# bank_35.net
KiCad netlist of a schematic drawn in Altium Designer
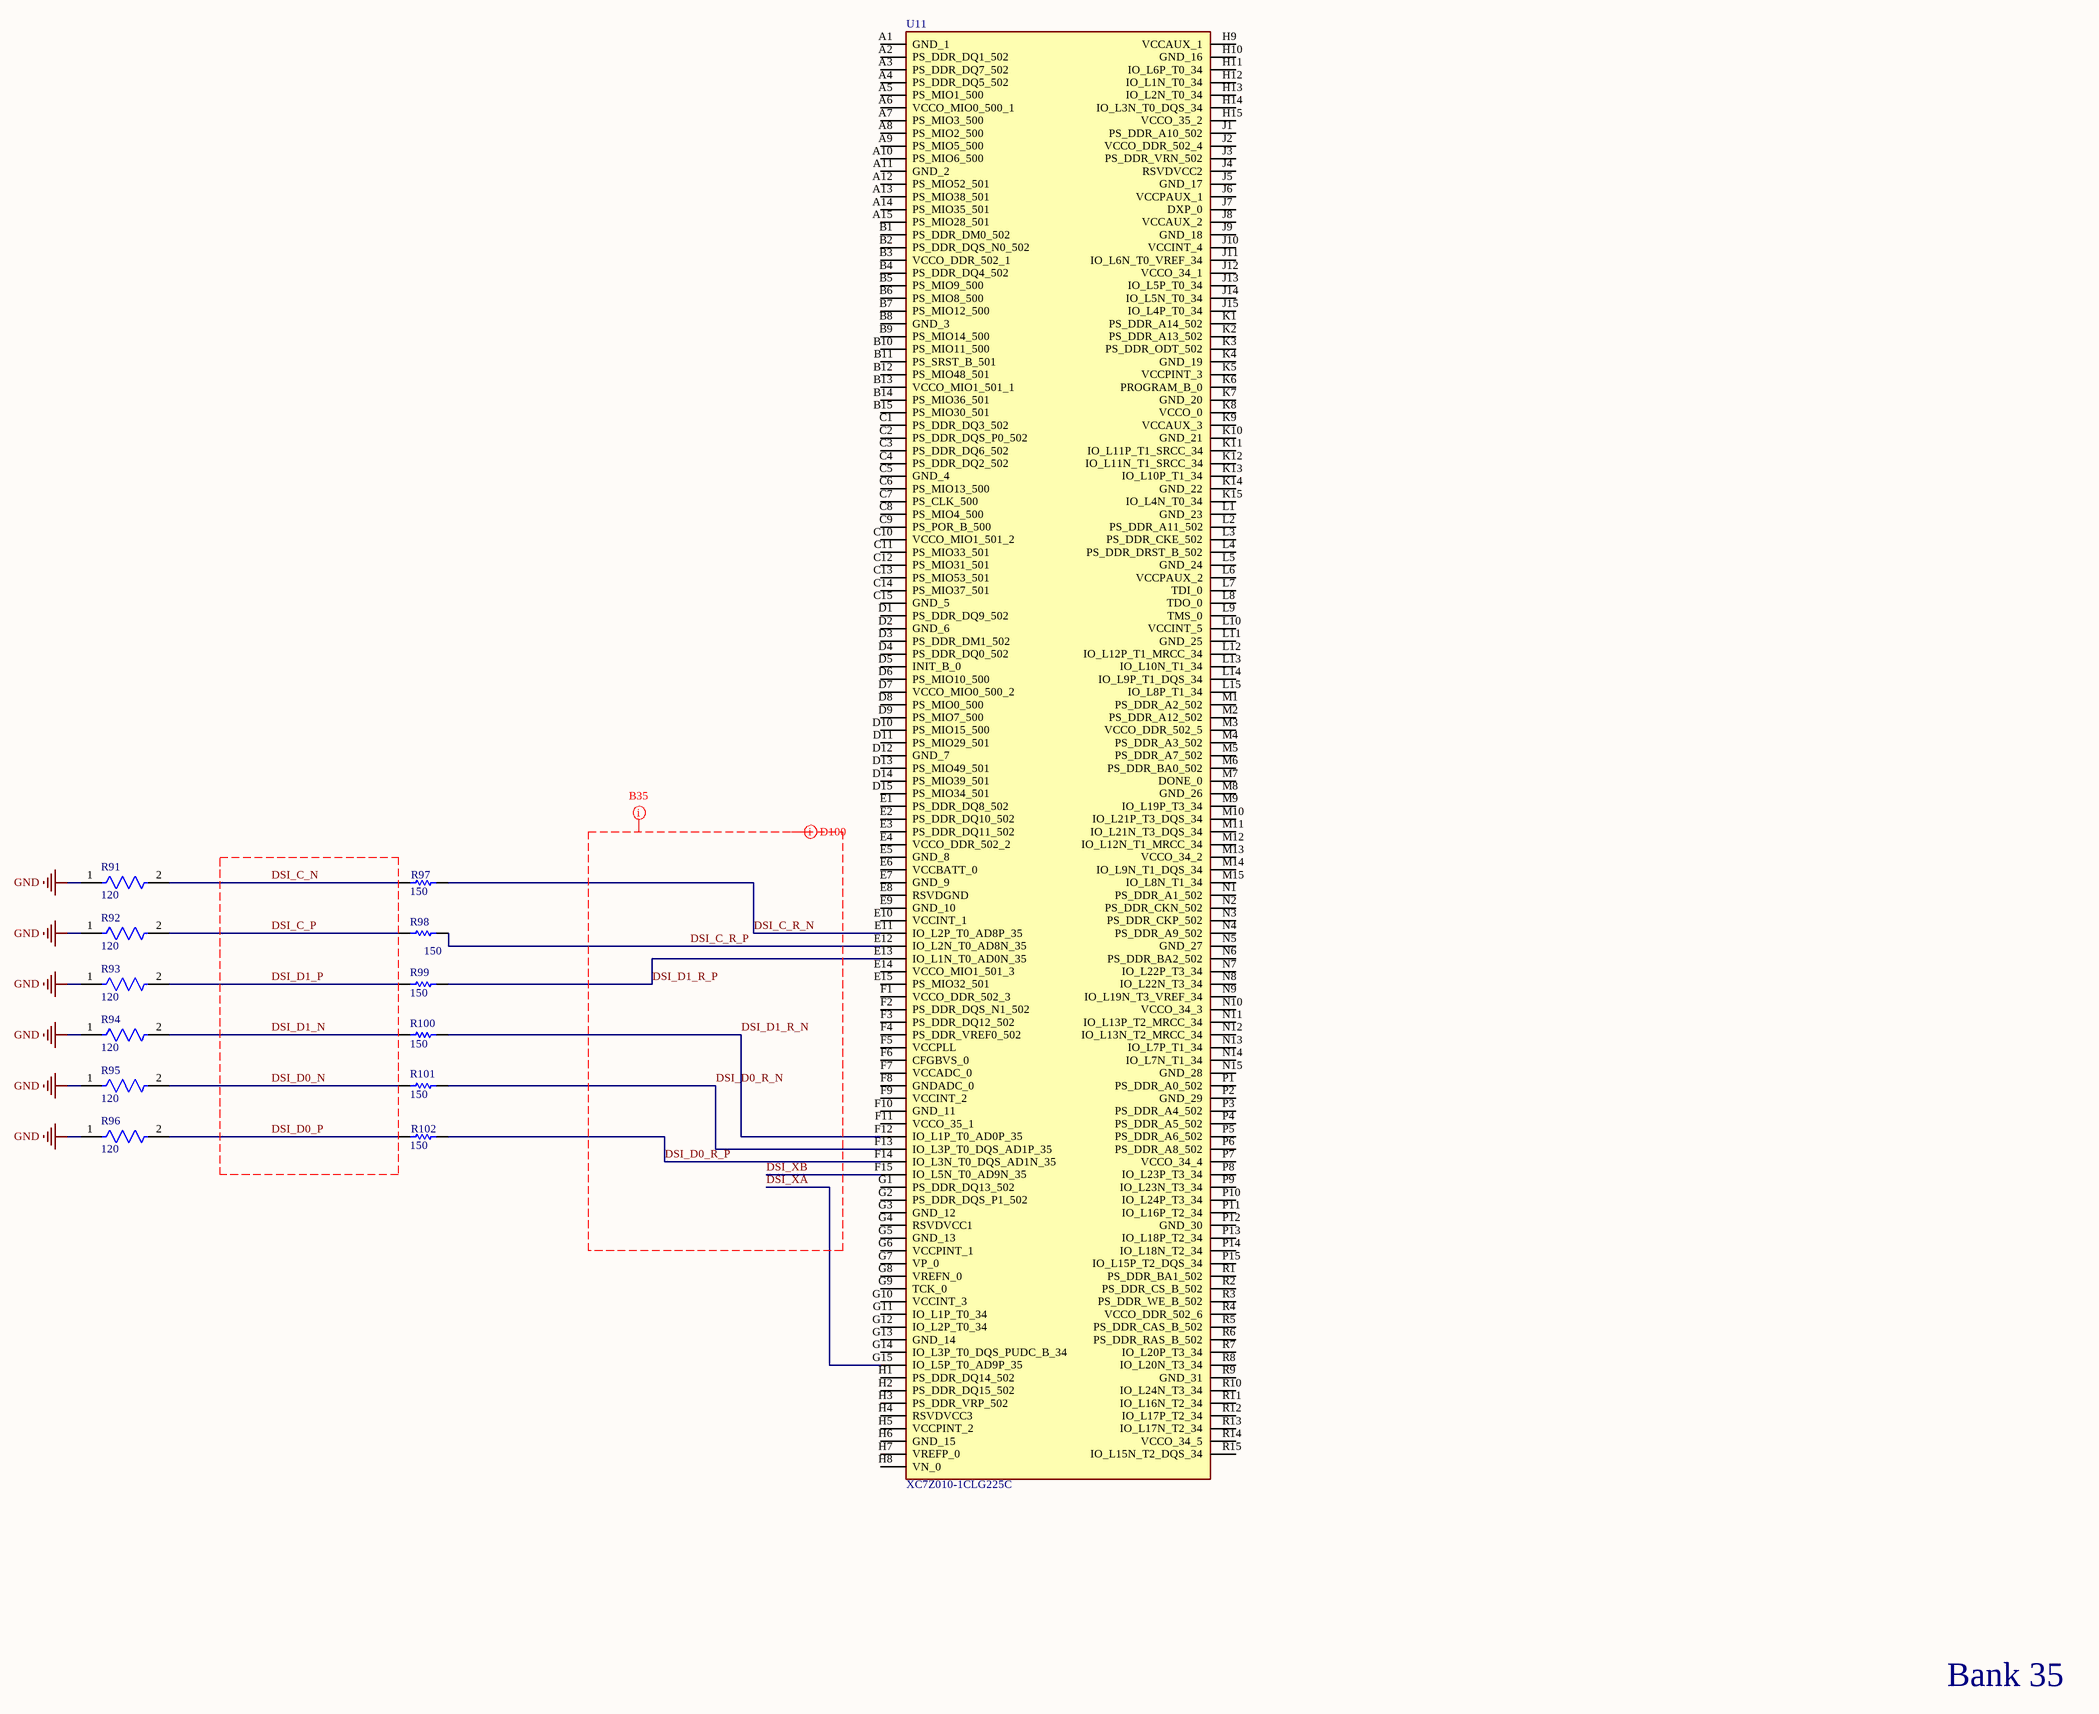
[diagram p0: bank 35.SchDoc]

(export (version "E")
  (design (tool "Eeschema 10.0.6"))
  (components
    (comp (ref "R91")
      (value "120")
      (footprint "FP-CR1206-MFG")
      (description "Thick Film Chip Resistors 1206 120Ω 0.25W 1% 100ppm/°C")
      (fields (field (name "TOLERANCE") "1%"))
      (libsource (lib "Altium Content Vault") (part "1029c3af85768c4190bb7ad29bc67b5"))
    )
    (comp (ref "R92")
      (value "120")
      (footprint "FP-CR1206-MFG")
      (description "Thick Film Chip Resistors 1206 120Ω 0.25W 1% 100ppm/°C")
      (fields (field (name "TOLERANCE") "1%"))
      (libsource (lib "Altium Content Vault") (part "1029c3af85768c4190bb7ad29bc67b5"))
    )
    (comp (ref "R93")
      (value "120")
      (footprint "FP-CR1206-MFG")
      (description "Thick Film Chip Resistors 1206 120Ω 0.25W 1% 100ppm/°C")
      (fields (field (name "TOLERANCE") "1%"))
      (libsource (lib "Altium Content Vault") (part "1029c3af85768c4190bb7ad29bc67b5"))
    )
    (comp (ref "R94")
      (value "120")
      (footprint "FP-CR1206-MFG")
      (description "Thick Film Chip Resistors 1206 120Ω 0.25W 1% 100ppm/°C")
      (fields (field (name "TOLERANCE") "1%"))
      (libsource (lib "Altium Content Vault") (part "1029c3af85768c4190bb7ad29bc67b5"))
    )
    (comp (ref "R95")
      (value "120")
      (footprint "FP-CR1206-MFG")
      (description "Thick Film Chip Resistors 1206 120Ω 0.25W 1% 100ppm/°C")
      (fields (field (name "TOLERANCE") "1%"))
      (libsource (lib "Altium Content Vault") (part "1029c3af85768c4190bb7ad29bc67b5"))
    )
    (comp (ref "R96")
      (value "120")
      (footprint "FP-CR1206-MFG")
      (description "Thick Film Chip Resistors 1206 120Ω 0.25W 1% 100ppm/°C")
      (fields (field (name "TOLERANCE") "1%"))
      (libsource (lib "Altium Content Vault") (part "1029c3af85768c4190bb7ad29bc67b5"))
    )
    (comp (ref "R97")
      (value "150")
      (footprint "RESC1609X55X30NL10T20")
      (fields (field (name "MANUFACTURER") "Vishay Dale") (field (name "PART NUMBER") "TNPW0603150RBETA"))
      (libsource (lib "Altium Content Vault") (part "RES"))
    )
    (comp (ref "R98")
      (value "150")
      (footprint "RESC1609X55X30NL10T20")
      (fields (field (name "MANUFACTURER") "Vishay Dale") (field (name "PART NUMBER") "TNPW0603150RBETA"))
      (libsource (lib "Altium Content Vault") (part "RES"))
    )
    (comp (ref "R99")
      (value "150")
      (footprint "RESC1609X55X30NL10T20")
      (fields (field (name "MANUFACTURER") "Vishay Dale") (field (name "PART NUMBER") "TNPW0603150RBETA"))
      (libsource (lib "Altium Content Vault") (part "RES"))
    )
    (comp (ref "R100")
      (value "150")
      (footprint "RESC1609X55X30NL10T20")
      (fields (field (name "MANUFACTURER") "Vishay Dale") (field (name "PART NUMBER") "TNPW0603150RBETA"))
      (libsource (lib "Altium Content Vault") (part "RES"))
    )
    (comp (ref "R101")
      (value "150")
      (footprint "RESC1609X55X30NL10T20")
      (fields (field (name "MANUFACTURER") "Vishay Dale") (field (name "PART NUMBER") "TNPW0603150RBETA"))
      (libsource (lib "Altium Content Vault") (part "RES"))
    )
    (comp (ref "R102")
      (value "150")
      (footprint "RESC1609X55X30NL10T20")
      (fields (field (name "MANUFACTURER") "Vishay Dale") (field (name "PART NUMBER") "TNPW0603150RBETA"))
      (libsource (lib "Altium Content Vault") (part "RES"))
    )
    (comp (ref "U11")
      (value "XC7Z010-1CLG225C")
      (footprint "SamacSys:BGA225C80P15X15_1300X1300X140")
      (description "Integrated Circuit")
      (fields (field (name "MOUSER PART NUMBER") "217-XC7Z010-1CLG225C"))
      (libsource (lib "*") (part "XC7Z010-1CLG225C"))
    )
  )
  (nets
    (net (code "1") (name "/DSI_C_N") (class "Default")
      (node (ref "R91") (pin "2") (pinfunction "2_2") (pintype "passive"))
      (node (ref "R97") (pin "1") (pinfunction "1_1") (pintype "passive"))
    )
    (net (code "2") (name "/DSI_C_P") (class "Default")
      (node (ref "R92") (pin "2") (pinfunction "2_2") (pintype "passive"))
      (node (ref "R98") (pin "1") (pinfunction "1_1") (pintype "passive"))
    )
    (net (code "3") (name "/DSI_C_R_N") (class "Default")
      (node (ref "R97") (pin "2") (pinfunction "2_2") (pintype "passive"))
      (node (ref "U11") (pin "E11") (pinfunction "IO_L2P_T0_AD8P_35_E11") (pintype "passive"))
    )
    (net (code "4") (name "/DSI_C_R_P") (class "Default")
      (node (ref "R98") (pin "2") (pinfunction "2_2") (pintype "passive"))
      (node (ref "U11") (pin "E12") (pinfunction "IO_L2N_T0_AD8N_35_E12") (pintype "passive"))
    )
    (net (code "5") (name "/DSI_D0_N") (class "Default")
      (node (ref "R101") (pin "1") (pinfunction "1_1") (pintype "passive"))
      (node (ref "R95") (pin "2") (pinfunction "2_2") (pintype "passive"))
    )
    (net (code "6") (name "/DSI_D0_P") (class "Default")
      (node (ref "R102") (pin "1") (pinfunction "1_1") (pintype "passive"))
      (node (ref "R96") (pin "2") (pinfunction "2_2") (pintype "passive"))
    )
    (net (code "7") (name "/DSI_D0_R_N") (class "Default")
      (node (ref "R101") (pin "2") (pinfunction "2_2") (pintype "passive"))
      (node (ref "U11") (pin "F13") (pinfunction "IO_L3P_T0_DQS_AD1P_35_F13") (pintype "passive"))
    )
    (net (code "8") (name "/DSI_D0_R_P") (class "Default")
      (node (ref "R102") (pin "2") (pinfunction "2_2") (pintype "passive"))
      (node (ref "U11") (pin "F14") (pinfunction "IO_L3N_T0_DQS_AD1N_35_F14") (pintype "passive"))
    )
    (net (code "9") (name "/DSI_D1_N") (class "Default")
      (node (ref "R100") (pin "1") (pinfunction "1_1") (pintype "passive"))
      (node (ref "R94") (pin "2") (pinfunction "2_2") (pintype "passive"))
    )
    (net (code "10") (name "/DSI_D1_P") (class "Default")
      (node (ref "R93") (pin "2") (pinfunction "2_2") (pintype "passive"))
      (node (ref "R99") (pin "1") (pinfunction "1_1") (pintype "passive"))
    )
    (net (code "11") (name "/DSI_D1_R_N") (class "Default")
      (node (ref "R100") (pin "2") (pinfunction "2_2") (pintype "passive"))
      (node (ref "U11") (pin "F12") (pinfunction "IO_L1P_T0_AD0P_35_F12") (pintype "passive"))
    )
    (net (code "12") (name "/DSI_D1_R_P") (class "Default")
      (node (ref "R99") (pin "2") (pinfunction "2_2") (pintype "passive"))
      (node (ref "U11") (pin "E13") (pinfunction "IO_L1N_T0_AD0N_35_E13") (pintype "passive"))
    )
    (net (code "13") (name "/DSI_XA") (class "Default")
      (node (ref "U11") (pin "G15") (pinfunction "IO_L5P_T0_AD9P_35_G15") (pintype "passive"))
    )
    (net (code "14") (name "/DSI_XB") (class "Default")
      (node (ref "U11") (pin "F15") (pinfunction "IO_L5N_T0_AD9N_35_F15") (pintype "passive"))
    )
    (net (code "15") (name "GND") (class "Default")
      (node (ref "R91") (pin "1") (pinfunction "1_1") (pintype "passive"))
      (node (ref "R92") (pin "1") (pinfunction "1_1") (pintype "passive"))
      (node (ref "R93") (pin "1") (pinfunction "1_1") (pintype "passive"))
      (node (ref "R94") (pin "1") (pinfunction "1_1") (pintype "passive"))
      (node (ref "R95") (pin "1") (pinfunction "1_1") (pintype "passive"))
      (node (ref "R96") (pin "1") (pinfunction "1_1") (pintype "passive"))
    )
    (net (code "16") (name "unconnected-(U11-CFGBVS_0-PadF6)") (class "Default")
      (node (ref "U11") (pin "F6") (pinfunction "CFGBVS_0_F6") (pintype "passive"))
    )
    (net (code "17") (name "unconnected-(U11-DONE_0-PadM7)") (class "Default")
      (node (ref "U11") (pin "M7") (pinfunction "DONE_0_M7") (pintype "passive"))
    )
    (net (code "18") (name "unconnected-(U11-DXP_0-PadJ7)") (class "Default")
      (node (ref "U11") (pin "J7") (pinfunction "DXP_0_J7") (pintype "passive"))
    )
    (net (code "19") (name "unconnected-(U11-GNDADC_0-PadF8)") (class "Default")
      (node (ref "U11") (pin "F8") (pinfunction "GNDADC_0_F8") (pintype "passive"))
    )
    (net (code "20") (name "unconnected-(U11-GND_1-PadA1)") (class "Default")
      (node (ref "U11") (pin "A1") (pinfunction "GND_1_A1") (pintype "passive"))
    )
    (net (code "21") (name "unconnected-(U11-GND_2-PadA11)") (class "Default")
      (node (ref "U11") (pin "A11") (pinfunction "GND_2_A11") (pintype "passive"))
    )
    (net (code "22") (name "unconnected-(U11-GND_3-PadB8)") (class "Default")
      (node (ref "U11") (pin "B8") (pinfunction "GND_3_B8") (pintype "passive"))
    )
    (net (code "23") (name "unconnected-(U11-GND_4-PadC5)") (class "Default")
      (node (ref "U11") (pin "C5") (pinfunction "GND_4_C5") (pintype "passive"))
    )
    (net (code "24") (name "unconnected-(U11-GND_5-PadC15)") (class "Default")
      (node (ref "U11") (pin "C15") (pinfunction "GND_5_C15") (pintype "passive"))
    )
    (net (code "25") (name "unconnected-(U11-GND_6-PadD2)") (class "Default")
      (node (ref "U11") (pin "D2") (pinfunction "GND_6_D2") (pintype "passive"))
    )
    (net (code "26") (name "unconnected-(U11-GND_7-PadD12)") (class "Default")
      (node (ref "U11") (pin "D12") (pinfunction "GND_7_D12") (pintype "passive"))
    )
    (net (code "27") (name "unconnected-(U11-GND_8-PadE5)") (class "Default")
      (node (ref "U11") (pin "E5") (pinfunction "GND_8_E5") (pintype "passive"))
    )
    (net (code "28") (name "unconnected-(U11-GND_9-PadE7)") (class "Default")
      (node (ref "U11") (pin "E7") (pinfunction "GND_9_E7") (pintype "passive"))
    )
    (net (code "29") (name "unconnected-(U11-GND_10-PadE9)") (class "Default")
      (node (ref "U11") (pin "E9") (pinfunction "GND_10_E9") (pintype "passive"))
    )
    (net (code "30") (name "unconnected-(U11-GND_11-PadF10)") (class "Default")
      (node (ref "U11") (pin "F10") (pinfunction "GND_11_F10") (pintype "passive"))
    )
    (net (code "31") (name "unconnected-(U11-GND_12-PadG3)") (class "Default")
      (node (ref "U11") (pin "G3") (pinfunction "GND_12_G3") (pintype "passive"))
    )
    (net (code "32") (name "unconnected-(U11-GND_13-PadG5)") (class "Default")
      (node (ref "U11") (pin "G5") (pinfunction "GND_13_G5") (pintype "passive"))
    )
    (net (code "33") (name "unconnected-(U11-GND_14-PadG13)") (class "Default")
      (node (ref "U11") (pin "G13") (pinfunction "GND_14_G13") (pintype "passive"))
    )
    (net (code "34") (name "unconnected-(U11-GND_15-PadH6)") (class "Default")
      (node (ref "U11") (pin "H6") (pinfunction "GND_15_H6") (pintype "passive"))
    )
    (net (code "35") (name "unconnected-(U11-GND_16-PadH10)") (class "Default")
      (node (ref "U11") (pin "H10") (pinfunction "GND_16_H10") (pintype "passive"))
    )
    (net (code "36") (name "unconnected-(U11-GND_17-PadJ5)") (class "Default")
      (node (ref "U11") (pin "J5") (pinfunction "GND_17_J5") (pintype "passive"))
    )
    (net (code "37") (name "unconnected-(U11-GND_18-PadJ9)") (class "Default")
      (node (ref "U11") (pin "J9") (pinfunction "GND_18_J9") (pintype "passive"))
    )
    (net (code "38") (name "unconnected-(U11-GND_19-PadK4)") (class "Default")
      (node (ref "U11") (pin "K4") (pinfunction "GND_19_K4") (pintype "passive"))
    )
    (net (code "39") (name "unconnected-(U11-GND_20-PadK7)") (class "Default")
      (node (ref "U11") (pin "K7") (pinfunction "GND_20_K7") (pintype "passive"))
    )
    (net (code "40") (name "unconnected-(U11-GND_21-PadK10)") (class "Default")
      (node (ref "U11") (pin "K10") (pinfunction "GND_21_K10") (pintype "passive"))
    )
    (net (code "41") (name "unconnected-(U11-GND_22-PadK14)") (class "Default")
      (node (ref "U11") (pin "K14") (pinfunction "GND_22_K14") (pintype "passive"))
    )
    (net (code "42") (name "unconnected-(U11-GND_23-PadL1)") (class "Default")
      (node (ref "U11") (pin "L1") (pinfunction "GND_23_L1") (pintype "passive"))
    )
    (net (code "43") (name "unconnected-(U11-GND_24-PadL5)") (class "Default")
      (node (ref "U11") (pin "L5") (pinfunction "GND_24_L5") (pintype "passive"))
    )
    (net (code "44") (name "unconnected-(U11-GND_25-PadL11)") (class "Default")
      (node (ref "U11") (pin "L11") (pinfunction "GND_25_L11") (pintype "passive"))
    )
    (net (code "45") (name "unconnected-(U11-GND_26-PadM8)") (class "Default")
      (node (ref "U11") (pin "M8") (pinfunction "GND_26_M8") (pintype "passive"))
    )
    (net (code "46") (name "unconnected-(U11-GND_27-PadN5)") (class "Default")
      (node (ref "U11") (pin "N5") (pinfunction "GND_27_N5") (pintype "passive"))
    )
    (net (code "47") (name "unconnected-(U11-GND_28-PadN15)") (class "Default")
      (node (ref "U11") (pin "N15") (pinfunction "GND_28_N15") (pintype "passive"))
    )
    (net (code "48") (name "unconnected-(U11-GND_29-PadP2)") (class "Default")
      (node (ref "U11") (pin "P2") (pinfunction "GND_29_P2") (pintype "passive"))
    )
    (net (code "49") (name "unconnected-(U11-GND_30-PadP12)") (class "Default")
      (node (ref "U11") (pin "P12") (pinfunction "GND_30_P12") (pintype "passive"))
    )
    (net (code "50") (name "unconnected-(U11-GND_31-PadR9)") (class "Default")
      (node (ref "U11") (pin "R9") (pinfunction "GND_31_R9") (pintype "passive"))
    )
    (net (code "51") (name "unconnected-(U11-INIT_B_0-PadD5)") (class "Default")
      (node (ref "U11") (pin "D5") (pinfunction "INIT_B_0_D5") (pintype "passive"))
    )
    (net (code "52") (name "unconnected-(U11-IO_L1N_T0_34-PadH12)") (class "Default")
      (node (ref "U11") (pin "H12") (pinfunction "IO_L1N_T0_34_H12") (pintype "passive"))
    )
    (net (code "53") (name "unconnected-(U11-IO_L1P_T0_34-PadG11)") (class "Default")
      (node (ref "U11") (pin "G11") (pinfunction "IO_L1P_T0_34_G11") (pintype "passive"))
    )
    (net (code "54") (name "unconnected-(U11-IO_L2N_T0_34-PadH13)") (class "Default")
      (node (ref "U11") (pin "H13") (pinfunction "IO_L2N_T0_34_H13") (pintype "passive"))
    )
    (net (code "55") (name "unconnected-(U11-IO_L2P_T0_34-PadG12)") (class "Default")
      (node (ref "U11") (pin "G12") (pinfunction "IO_L2P_T0_34_G12") (pintype "passive"))
    )
    (net (code "56") (name "unconnected-(U11-IO_L3N_T0_DQS_34-PadH14)") (class "Default")
      (node (ref "U11") (pin "H14") (pinfunction "IO_L3N_T0_DQS_34_H14") (pintype "passive"))
    )
    (net (code "57") (name "unconnected-(U11-IO_L3P_T0_DQS_PUDC_B_34-PadG14)") (class "Default")
      (node (ref "U11") (pin "G14") (pinfunction "IO_L3P_T0_DQS_PUDC_B_34_G14") (pintype "passive"))
    )
    (net (code "58") (name "unconnected-(U11-IO_L4N_T0_34-PadK15)") (class "Default")
      (node (ref "U11") (pin "K15") (pinfunction "IO_L4N_T0_34_K15") (pintype "passive"))
    )
    (net (code "59") (name "unconnected-(U11-IO_L4P_T0_34-PadJ15)") (class "Default")
      (node (ref "U11") (pin "J15") (pinfunction "IO_L4P_T0_34_J15") (pintype "passive"))
    )
    (net (code "60") (name "unconnected-(U11-IO_L5N_T0_34-PadJ14)") (class "Default")
      (node (ref "U11") (pin "J14") (pinfunction "IO_L5N_T0_34_J14") (pintype "passive"))
    )
    (net (code "61") (name "unconnected-(U11-IO_L5P_T0_34-PadJ13)") (class "Default")
      (node (ref "U11") (pin "J13") (pinfunction "IO_L5P_T0_34_J13") (pintype "passive"))
    )
    (net (code "62") (name "unconnected-(U11-IO_L6N_T0_VREF_34-PadJ11)") (class "Default")
      (node (ref "U11") (pin "J11") (pinfunction "IO_L6N_T0_VREF_34_J11") (pintype "passive"))
    )
    (net (code "63") (name "unconnected-(U11-IO_L6P_T0_34-PadH11)") (class "Default")
      (node (ref "U11") (pin "H11") (pinfunction "IO_L6P_T0_34_H11") (pintype "passive"))
    )
    (net (code "64") (name "unconnected-(U11-IO_L7N_T1_34-PadN14)") (class "Default")
      (node (ref "U11") (pin "N14") (pinfunction "IO_L7N_T1_34_N14") (pintype "passive"))
    )
    (net (code "65") (name "unconnected-(U11-IO_L7P_T1_34-PadN13)") (class "Default")
      (node (ref "U11") (pin "N13") (pinfunction "IO_L7P_T1_34_N13") (pintype "passive"))
    )
    (net (code "66") (name "unconnected-(U11-IO_L8N_T1_34-PadM15)") (class "Default")
      (node (ref "U11") (pin "M15") (pinfunction "IO_L8N_T1_34_M15") (pintype "passive"))
    )
    (net (code "67") (name "unconnected-(U11-IO_L8P_T1_34-PadL15)") (class "Default")
      (node (ref "U11") (pin "L15") (pinfunction "IO_L8P_T1_34_L15") (pintype "passive"))
    )
    (net (code "68") (name "unconnected-(U11-IO_L9N_T1_DQS_34-PadM14)") (class "Default")
      (node (ref "U11") (pin "M14") (pinfunction "IO_L9N_T1_DQS_34_M14") (pintype "passive"))
    )
    (net (code "69") (name "unconnected-(U11-IO_L9P_T1_DQS_34-PadL14)") (class "Default")
      (node (ref "U11") (pin "L14") (pinfunction "IO_L9P_T1_DQS_34_L14") (pintype "passive"))
    )
    (net (code "70") (name "unconnected-(U11-IO_L10N_T1_34-PadL13)") (class "Default")
      (node (ref "U11") (pin "L13") (pinfunction "IO_L10N_T1_34_L13") (pintype "passive"))
    )
    (net (code "71") (name "unconnected-(U11-IO_L10P_T1_34-PadK13)") (class "Default")
      (node (ref "U11") (pin "K13") (pinfunction "IO_L10P_T1_34_K13") (pintype "passive"))
    )
    (net (code "72") (name "unconnected-(U11-IO_L11N_T1_SRCC_34-PadK12)") (class "Default")
      (node (ref "U11") (pin "K12") (pinfunction "IO_L11N_T1_SRCC_34_K12") (pintype "passive"))
    )
    (net (code "73") (name "unconnected-(U11-IO_L11P_T1_SRCC_34-PadK11)") (class "Default")
      (node (ref "U11") (pin "K11") (pinfunction "IO_L11P_T1_SRCC_34_K11") (pintype "passive"))
    )
    (net (code "74") (name "unconnected-(U11-IO_L12N_T1_MRCC_34-PadM12)") (class "Default")
      (node (ref "U11") (pin "M12") (pinfunction "IO_L12N_T1_MRCC_34_M12") (pintype "passive"))
    )
    (net (code "75") (name "unconnected-(U11-IO_L12P_T1_MRCC_34-PadL12)") (class "Default")
      (node (ref "U11") (pin "L12") (pinfunction "IO_L12P_T1_MRCC_34_L12") (pintype "passive"))
    )
    (net (code "76") (name "unconnected-(U11-IO_L13N_T2_MRCC_34-PadN12)") (class "Default")
      (node (ref "U11") (pin "N12") (pinfunction "IO_L13N_T2_MRCC_34_N12") (pintype "passive"))
    )
    (net (code "77") (name "unconnected-(U11-IO_L13P_T2_MRCC_34-PadN11)") (class "Default")
      (node (ref "U11") (pin "N11") (pinfunction "IO_L13P_T2_MRCC_34_N11") (pintype "passive"))
    )
    (net (code "78") (name "unconnected-(U11-IO_L15N_T2_DQS_34-PadR15)") (class "Default")
      (node (ref "U11") (pin "R15") (pinfunction "IO_L15N_T2_DQS_34_R15") (pintype "passive"))
    )
    (net (code "79") (name "unconnected-(U11-IO_L15P_T2_DQS_34-PadP15)") (class "Default")
      (node (ref "U11") (pin "P15") (pinfunction "IO_L15P_T2_DQS_34_P15") (pintype "passive"))
    )
    (net (code "80") (name "unconnected-(U11-IO_L16N_T2_34-PadR11)") (class "Default")
      (node (ref "U11") (pin "R11") (pinfunction "IO_L16N_T2_34_R11") (pintype "passive"))
    )
    (net (code "81") (name "unconnected-(U11-IO_L16P_T2_34-PadP11)") (class "Default")
      (node (ref "U11") (pin "P11") (pinfunction "IO_L16P_T2_34_P11") (pintype "passive"))
    )
    (net (code "82") (name "unconnected-(U11-IO_L17N_T2_34-PadR13)") (class "Default")
      (node (ref "U11") (pin "R13") (pinfunction "IO_L17N_T2_34_R13") (pintype "passive"))
    )
    (net (code "83") (name "unconnected-(U11-IO_L17P_T2_34-PadR12)") (class "Default")
      (node (ref "U11") (pin "R12") (pinfunction "IO_L17P_T2_34_R12") (pintype "passive"))
    )
    (net (code "84") (name "unconnected-(U11-IO_L18N_T2_34-PadP14)") (class "Default")
      (node (ref "U11") (pin "P14") (pinfunction "IO_L18N_T2_34_P14") (pintype "passive"))
    )
    (net (code "85") (name "unconnected-(U11-IO_L18P_T2_34-PadP13)") (class "Default")
      (node (ref "U11") (pin "P13") (pinfunction "IO_L18P_T2_34_P13") (pintype "passive"))
    )
    (net (code "86") (name "unconnected-(U11-IO_L19N_T3_VREF_34-PadN9)") (class "Default")
      (node (ref "U11") (pin "N9") (pinfunction "IO_L19N_T3_VREF_34_N9") (pintype "passive"))
    )
    (net (code "87") (name "unconnected-(U11-IO_L19P_T3_34-PadM9)") (class "Default")
      (node (ref "U11") (pin "M9") (pinfunction "IO_L19P_T3_34_M9") (pintype "passive"))
    )
    (net (code "88") (name "unconnected-(U11-IO_L20N_T3_34-PadR8)") (class "Default")
      (node (ref "U11") (pin "R8") (pinfunction "IO_L20N_T3_34_R8") (pintype "passive"))
    )
    (net (code "89") (name "unconnected-(U11-IO_L20P_T3_34-PadR7)") (class "Default")
      (node (ref "U11") (pin "R7") (pinfunction "IO_L20P_T3_34_R7") (pintype "passive"))
    )
    (net (code "90") (name "unconnected-(U11-IO_L21N_T3_DQS_34-PadM11)") (class "Default")
      (node (ref "U11") (pin "M11") (pinfunction "IO_L21N_T3_DQS_34_M11") (pintype "passive"))
    )
    (net (code "91") (name "unconnected-(U11-IO_L21P_T3_DQS_34-PadM10)") (class "Default")
      (node (ref "U11") (pin "M10") (pinfunction "IO_L21P_T3_DQS_34_M10") (pintype "passive"))
    )
    (net (code "92") (name "unconnected-(U11-IO_L22N_T3_34-PadN8)") (class "Default")
      (node (ref "U11") (pin "N8") (pinfunction "IO_L22N_T3_34_N8") (pintype "passive"))
    )
    (net (code "93") (name "unconnected-(U11-IO_L22P_T3_34-PadN7)") (class "Default")
      (node (ref "U11") (pin "N7") (pinfunction "IO_L22P_T3_34_N7") (pintype "passive"))
    )
    (net (code "94") (name "unconnected-(U11-IO_L23N_T3_34-PadP9)") (class "Default")
      (node (ref "U11") (pin "P9") (pinfunction "IO_L23N_T3_34_P9") (pintype "passive"))
    )
    (net (code "95") (name "unconnected-(U11-IO_L23P_T3_34-PadP8)") (class "Default")
      (node (ref "U11") (pin "P8") (pinfunction "IO_L23P_T3_34_P8") (pintype "passive"))
    )
    (net (code "96") (name "unconnected-(U11-IO_L24N_T3_34-PadR10)") (class "Default")
      (node (ref "U11") (pin "R10") (pinfunction "IO_L24N_T3_34_R10") (pintype "passive"))
    )
    (net (code "97") (name "unconnected-(U11-IO_L24P_T3_34-PadP10)") (class "Default")
      (node (ref "U11") (pin "P10") (pinfunction "IO_L24P_T3_34_P10") (pintype "passive"))
    )
    (net (code "98") (name "unconnected-(U11-PROGRAM_B_0-PadK6)") (class "Default")
      (node (ref "U11") (pin "K6") (pinfunction "PROGRAM_B_0_K6") (pintype "passive"))
    )
    (net (code "99") (name "unconnected-(U11-PS_CLK_500-PadC7)") (class "Default")
      (node (ref "U11") (pin "C7") (pinfunction "PS_CLK_500_C7") (pintype "passive"))
    )
    (net (code "100") (name "unconnected-(U11-PS_DDR_A0_502-PadP1)") (class "Default")
      (node (ref "U11") (pin "P1") (pinfunction "PS_DDR_A0_502_P1") (pintype "passive"))
    )
    (net (code "101") (name "unconnected-(U11-PS_DDR_A1_502-PadN1)") (class "Default")
      (node (ref "U11") (pin "N1") (pinfunction "PS_DDR_A1_502_N1") (pintype "passive"))
    )
    (net (code "102") (name "unconnected-(U11-PS_DDR_A2_502-PadM1)") (class "Default")
      (node (ref "U11") (pin "M1") (pinfunction "PS_DDR_A2_502_M1") (pintype "passive"))
    )
    (net (code "103") (name "unconnected-(U11-PS_DDR_A3_502-PadM4)") (class "Default")
      (node (ref "U11") (pin "M4") (pinfunction "PS_DDR_A3_502_M4") (pintype "passive"))
    )
    (net (code "104") (name "unconnected-(U11-PS_DDR_A4_502-PadP3)") (class "Default")
      (node (ref "U11") (pin "P3") (pinfunction "PS_DDR_A4_502_P3") (pintype "passive"))
    )
    (net (code "105") (name "unconnected-(U11-PS_DDR_A5_502-PadP4)") (class "Default")
      (node (ref "U11") (pin "P4") (pinfunction "PS_DDR_A5_502_P4") (pintype "passive"))
    )
    (net (code "106") (name "unconnected-(U11-PS_DDR_A6_502-PadP5)") (class "Default")
      (node (ref "U11") (pin "P5") (pinfunction "PS_DDR_A6_502_P5") (pintype "passive"))
    )
    (net (code "107") (name "unconnected-(U11-PS_DDR_A7_502-PadM5)") (class "Default")
      (node (ref "U11") (pin "M5") (pinfunction "PS_DDR_A7_502_M5") (pintype "passive"))
    )
    (net (code "108") (name "unconnected-(U11-PS_DDR_A8_502-PadP6)") (class "Default")
      (node (ref "U11") (pin "P6") (pinfunction "PS_DDR_A8_502_P6") (pintype "passive"))
    )
    (net (code "109") (name "unconnected-(U11-PS_DDR_A9_502-PadN4)") (class "Default")
      (node (ref "U11") (pin "N4") (pinfunction "PS_DDR_A9_502_N4") (pintype "passive"))
    )
    (net (code "110") (name "unconnected-(U11-PS_DDR_A10_502-PadJ1)") (class "Default")
      (node (ref "U11") (pin "J1") (pinfunction "PS_DDR_A10_502_J1") (pintype "passive"))
    )
    (net (code "111") (name "unconnected-(U11-PS_DDR_A11_502-PadL2)") (class "Default")
      (node (ref "U11") (pin "L2") (pinfunction "PS_DDR_A11_502_L2") (pintype "passive"))
    )
    (net (code "112") (name "unconnected-(U11-PS_DDR_A12_502-PadM2)") (class "Default")
      (node (ref "U11") (pin "M2") (pinfunction "PS_DDR_A12_502_M2") (pintype "passive"))
    )
    (net (code "113") (name "unconnected-(U11-PS_DDR_A13_502-PadK2)") (class "Default")
      (node (ref "U11") (pin "K2") (pinfunction "PS_DDR_A13_502_K2") (pintype "passive"))
    )
    (net (code "114") (name "unconnected-(U11-PS_DDR_A14_502-PadK1)") (class "Default")
      (node (ref "U11") (pin "K1") (pinfunction "PS_DDR_A14_502_K1") (pintype "passive"))
    )
    (net (code "115") (name "unconnected-(U11-PS_DDR_BA0_502-PadM6)") (class "Default")
      (node (ref "U11") (pin "M6") (pinfunction "PS_DDR_BA0_502_M6") (pintype "passive"))
    )
    (net (code "116") (name "unconnected-(U11-PS_DDR_BA1_502-PadR1)") (class "Default")
      (node (ref "U11") (pin "R1") (pinfunction "PS_DDR_BA1_502_R1") (pintype "passive"))
    )
    (net (code "117") (name "unconnected-(U11-PS_DDR_BA2_502-PadN6)") (class "Default")
      (node (ref "U11") (pin "N6") (pinfunction "PS_DDR_BA2_502_N6") (pintype "passive"))
    )
    (net (code "118") (name "unconnected-(U11-PS_DDR_CAS_B_502-PadR5)") (class "Default")
      (node (ref "U11") (pin "R5") (pinfunction "PS_DDR_CAS_B_502_R5") (pintype "passive"))
    )
    (net (code "119") (name "unconnected-(U11-PS_DDR_CKE_502-PadL3)") (class "Default")
      (node (ref "U11") (pin "L3") (pinfunction "PS_DDR_CKE_502_L3") (pintype "passive"))
    )
    (net (code "120") (name "unconnected-(U11-PS_DDR_CKN_502-PadN2)") (class "Default")
      (node (ref "U11") (pin "N2") (pinfunction "PS_DDR_CKN_502_N2") (pintype "passive"))
    )
    (net (code "121") (name "unconnected-(U11-PS_DDR_CKP_502-PadN3)") (class "Default")
      (node (ref "U11") (pin "N3") (pinfunction "PS_DDR_CKP_502_N3") (pintype "passive"))
    )
    (net (code "122") (name "unconnected-(U11-PS_DDR_CS_B_502-PadR2)") (class "Default")
      (node (ref "U11") (pin "R2") (pinfunction "PS_DDR_CS_B_502_R2") (pintype "passive"))
    )
    (net (code "123") (name "unconnected-(U11-PS_DDR_DM0_502-PadB1)") (class "Default")
      (node (ref "U11") (pin "B1") (pinfunction "PS_DDR_DM0_502_B1") (pintype "passive"))
    )
    (net (code "124") (name "unconnected-(U11-PS_DDR_DM1_502-PadD3)") (class "Default")
      (node (ref "U11") (pin "D3") (pinfunction "PS_DDR_DM1_502_D3") (pintype "passive"))
    )
    (net (code "125") (name "unconnected-(U11-PS_DDR_DQ0_502-PadD4)") (class "Default")
      (node (ref "U11") (pin "D4") (pinfunction "PS_DDR_DQ0_502_D4") (pintype "passive"))
    )
    (net (code "126") (name "unconnected-(U11-PS_DDR_DQ1_502-PadA2)") (class "Default")
      (node (ref "U11") (pin "A2") (pinfunction "PS_DDR_DQ1_502_A2") (pintype "passive"))
    )
    (net (code "127") (name "unconnected-(U11-PS_DDR_DQ2_502-PadC4)") (class "Default")
      (node (ref "U11") (pin "C4") (pinfunction "PS_DDR_DQ2_502_C4") (pintype "passive"))
    )
    (net (code "128") (name "unconnected-(U11-PS_DDR_DQ3_502-PadC1)") (class "Default")
      (node (ref "U11") (pin "C1") (pinfunction "PS_DDR_DQ3_502_C1") (pintype "passive"))
    )
    (net (code "129") (name "unconnected-(U11-PS_DDR_DQ4_502-PadB4)") (class "Default")
      (node (ref "U11") (pin "B4") (pinfunction "PS_DDR_DQ4_502_B4") (pintype "passive"))
    )
    (net (code "130") (name "unconnected-(U11-PS_DDR_DQ5_502-PadA4)") (class "Default")
      (node (ref "U11") (pin "A4") (pinfunction "PS_DDR_DQ5_502_A4") (pintype "passive"))
    )
    (net (code "131") (name "unconnected-(U11-PS_DDR_DQ6_502-PadC3)") (class "Default")
      (node (ref "U11") (pin "C3") (pinfunction "PS_DDR_DQ6_502_C3") (pintype "passive"))
    )
    (net (code "132") (name "unconnected-(U11-PS_DDR_DQ7_502-PadA3)") (class "Default")
      (node (ref "U11") (pin "A3") (pinfunction "PS_DDR_DQ7_502_A3") (pintype "passive"))
    )
    (net (code "133") (name "unconnected-(U11-PS_DDR_DQ8_502-PadE1)") (class "Default")
      (node (ref "U11") (pin "E1") (pinfunction "PS_DDR_DQ8_502_E1") (pintype "passive"))
    )
    (net (code "134") (name "unconnected-(U11-PS_DDR_DQ9_502-PadD1)") (class "Default")
      (node (ref "U11") (pin "D1") (pinfunction "PS_DDR_DQ9_502_D1") (pintype "passive"))
    )
    (net (code "135") (name "unconnected-(U11-PS_DDR_DQ10_502-PadE2)") (class "Default")
      (node (ref "U11") (pin "E2") (pinfunction "PS_DDR_DQ10_502_E2") (pintype "passive"))
    )
    (net (code "136") (name "unconnected-(U11-PS_DDR_DQ11_502-PadE3)") (class "Default")
      (node (ref "U11") (pin "E3") (pinfunction "PS_DDR_DQ11_502_E3") (pintype "passive"))
    )
    (net (code "137") (name "unconnected-(U11-PS_DDR_DQ12_502-PadF3)") (class "Default")
      (node (ref "U11") (pin "F3") (pinfunction "PS_DDR_DQ12_502_F3") (pintype "passive"))
    )
    (net (code "138") (name "unconnected-(U11-PS_DDR_DQ13_502-PadG1)") (class "Default")
      (node (ref "U11") (pin "G1") (pinfunction "PS_DDR_DQ13_502_G1") (pintype "passive"))
    )
    (net (code "139") (name "unconnected-(U11-PS_DDR_DQ14_502-PadH1)") (class "Default")
      (node (ref "U11") (pin "H1") (pinfunction "PS_DDR_DQ14_502_H1") (pintype "passive"))
    )
    (net (code "140") (name "unconnected-(U11-PS_DDR_DQ15_502-PadH2)") (class "Default")
      (node (ref "U11") (pin "H2") (pinfunction "PS_DDR_DQ15_502_H2") (pintype "passive"))
    )
    (net (code "141") (name "unconnected-(U11-PS_DDR_DQS_N0_502-PadB2)") (class "Default")
      (node (ref "U11") (pin "B2") (pinfunction "PS_DDR_DQS_N0_502_B2") (pintype "passive"))
    )
    (net (code "142") (name "unconnected-(U11-PS_DDR_DQS_N1_502-PadF2)") (class "Default")
      (node (ref "U11") (pin "F2") (pinfunction "PS_DDR_DQS_N1_502_F2") (pintype "passive"))
    )
    (net (code "143") (name "unconnected-(U11-PS_DDR_DQS_P0_502-PadC2)") (class "Default")
      (node (ref "U11") (pin "C2") (pinfunction "PS_DDR_DQS_P0_502_C2") (pintype "passive"))
    )
    (net (code "144") (name "unconnected-(U11-PS_DDR_DQS_P1_502-PadG2)") (class "Default")
      (node (ref "U11") (pin "G2") (pinfunction "PS_DDR_DQS_P1_502_G2") (pintype "passive"))
    )
    (net (code "145") (name "unconnected-(U11-PS_DDR_DRST_B_502-PadL4)") (class "Default")
      (node (ref "U11") (pin "L4") (pinfunction "PS_DDR_DRST_B_502_L4") (pintype "passive"))
    )
    (net (code "146") (name "unconnected-(U11-PS_DDR_ODT_502-PadK3)") (class "Default")
      (node (ref "U11") (pin "K3") (pinfunction "PS_DDR_ODT_502_K3") (pintype "passive"))
    )
    (net (code "147") (name "unconnected-(U11-PS_DDR_RAS_B_502-PadR6)") (class "Default")
      (node (ref "U11") (pin "R6") (pinfunction "PS_DDR_RAS_B_502_R6") (pintype "passive"))
    )
    (net (code "148") (name "unconnected-(U11-PS_DDR_VREF0_502-PadF4)") (class "Default")
      (node (ref "U11") (pin "F4") (pinfunction "PS_DDR_VREF0_502_F4") (pintype "passive"))
    )
    (net (code "149") (name "unconnected-(U11-PS_DDR_VRN_502-PadJ3)") (class "Default")
      (node (ref "U11") (pin "J3") (pinfunction "PS_DDR_VRN_502_J3") (pintype "passive"))
    )
    (net (code "150") (name "unconnected-(U11-PS_DDR_VRP_502-PadH3)") (class "Default")
      (node (ref "U11") (pin "H3") (pinfunction "PS_DDR_VRP_502_H3") (pintype "passive"))
    )
    (net (code "151") (name "unconnected-(U11-PS_DDR_WE_B_502-PadR3)") (class "Default")
      (node (ref "U11") (pin "R3") (pinfunction "PS_DDR_WE_B_502_R3") (pintype "passive"))
    )
    (net (code "152") (name "unconnected-(U11-PS_MIO0_500-PadD8)") (class "Default")
      (node (ref "U11") (pin "D8") (pinfunction "PS_MIO0_500_D8") (pintype "passive"))
    )
    (net (code "153") (name "unconnected-(U11-PS_MIO1_500-PadA5)") (class "Default")
      (node (ref "U11") (pin "A5") (pinfunction "PS_MIO1_500_A5") (pintype "passive"))
    )
    (net (code "154") (name "unconnected-(U11-PS_MIO2_500-PadA8)") (class "Default")
      (node (ref "U11") (pin "A8") (pinfunction "PS_MIO2_500_A8") (pintype "passive"))
    )
    (net (code "155") (name "unconnected-(U11-PS_MIO3_500-PadA7)") (class "Default")
      (node (ref "U11") (pin "A7") (pinfunction "PS_MIO3_500_A7") (pintype "passive"))
    )
    (net (code "156") (name "unconnected-(U11-PS_MIO4_500-PadC8)") (class "Default")
      (node (ref "U11") (pin "C8") (pinfunction "PS_MIO4_500_C8") (pintype "passive"))
    )
    (net (code "157") (name "unconnected-(U11-PS_MIO5_500-PadA9)") (class "Default")
      (node (ref "U11") (pin "A9") (pinfunction "PS_MIO5_500_A9") (pintype "passive"))
    )
    (net (code "158") (name "unconnected-(U11-PS_MIO6_500-PadA10)") (class "Default")
      (node (ref "U11") (pin "A10") (pinfunction "PS_MIO6_500_A10") (pintype "passive"))
    )
    (net (code "159") (name "unconnected-(U11-PS_MIO7_500-PadD9)") (class "Default")
      (node (ref "U11") (pin "D9") (pinfunction "PS_MIO7_500_D9") (pintype "passive"))
    )
    (net (code "160") (name "unconnected-(U11-PS_MIO8_500-PadB6)") (class "Default")
      (node (ref "U11") (pin "B6") (pinfunction "PS_MIO8_500_B6") (pintype "passive"))
    )
    (net (code "161") (name "unconnected-(U11-PS_MIO9_500-PadB5)") (class "Default")
      (node (ref "U11") (pin "B5") (pinfunction "PS_MIO9_500_B5") (pintype "passive"))
    )
    (net (code "162") (name "unconnected-(U11-PS_MIO10_500-PadD6)") (class "Default")
      (node (ref "U11") (pin "D6") (pinfunction "PS_MIO10_500_D6") (pintype "passive"))
    )
    (net (code "163") (name "unconnected-(U11-PS_MIO11_500-PadB10)") (class "Default")
      (node (ref "U11") (pin "B10") (pinfunction "PS_MIO11_500_B10") (pintype "passive"))
    )
    (net (code "164") (name "unconnected-(U11-PS_MIO12_500-PadB7)") (class "Default")
      (node (ref "U11") (pin "B7") (pinfunction "PS_MIO12_500_B7") (pintype "passive"))
    )
    (net (code "165") (name "unconnected-(U11-PS_MIO13_500-PadC6)") (class "Default")
      (node (ref "U11") (pin "C6") (pinfunction "PS_MIO13_500_C6") (pintype "passive"))
    )
    (net (code "166") (name "unconnected-(U11-PS_MIO14_500-PadB9)") (class "Default")
      (node (ref "U11") (pin "B9") (pinfunction "PS_MIO14_500_B9") (pintype "passive"))
    )
    (net (code "167") (name "unconnected-(U11-PS_MIO15_500-PadD10)") (class "Default")
      (node (ref "U11") (pin "D10") (pinfunction "PS_MIO15_500_D10") (pintype "passive"))
    )
    (net (code "168") (name "unconnected-(U11-PS_MIO28_501-PadA15)") (class "Default")
      (node (ref "U11") (pin "A15") (pinfunction "PS_MIO28_501_A15") (pintype "passive"))
    )
    (net (code "169") (name "unconnected-(U11-PS_MIO29_501-PadD11)") (class "Default")
      (node (ref "U11") (pin "D11") (pinfunction "PS_MIO29_501_D11") (pintype "passive"))
    )
    (net (code "170") (name "unconnected-(U11-PS_MIO30_501-PadB15)") (class "Default")
      (node (ref "U11") (pin "B15") (pinfunction "PS_MIO30_501_B15") (pintype "passive"))
    )
    (net (code "171") (name "unconnected-(U11-PS_MIO31_501-PadC12)") (class "Default")
      (node (ref "U11") (pin "C12") (pinfunction "PS_MIO31_501_C12") (pintype "passive"))
    )
    (net (code "172") (name "unconnected-(U11-PS_MIO32_501-PadE15)") (class "Default")
      (node (ref "U11") (pin "E15") (pinfunction "PS_MIO32_501_E15") (pintype "passive"))
    )
    (net (code "173") (name "unconnected-(U11-PS_MIO33_501-PadC11)") (class "Default")
      (node (ref "U11") (pin "C11") (pinfunction "PS_MIO33_501_C11") (pintype "passive"))
    )
    (net (code "174") (name "unconnected-(U11-PS_MIO34_501-PadD15)") (class "Default")
      (node (ref "U11") (pin "D15") (pinfunction "PS_MIO34_501_D15") (pintype "passive"))
    )
    (net (code "175") (name "unconnected-(U11-PS_MIO35_501-PadA14)") (class "Default")
      (node (ref "U11") (pin "A14") (pinfunction "PS_MIO35_501_A14") (pintype "passive"))
    )
    (net (code "176") (name "unconnected-(U11-PS_MIO36_501-PadB14)") (class "Default")
      (node (ref "U11") (pin "B14") (pinfunction "PS_MIO36_501_B14") (pintype "passive"))
    )
    (net (code "177") (name "unconnected-(U11-PS_MIO37_501-PadC14)") (class "Default")
      (node (ref "U11") (pin "C14") (pinfunction "PS_MIO37_501_C14") (pintype "passive"))
    )
    (net (code "178") (name "unconnected-(U11-PS_MIO38_501-PadA13)") (class "Default")
      (node (ref "U11") (pin "A13") (pinfunction "PS_MIO38_501_A13") (pintype "passive"))
    )
    (net (code "179") (name "unconnected-(U11-PS_MIO39_501-PadD14)") (class "Default")
      (node (ref "U11") (pin "D14") (pinfunction "PS_MIO39_501_D14") (pintype "passive"))
    )
    (net (code "180") (name "unconnected-(U11-PS_MIO48_501-PadB12)") (class "Default")
      (node (ref "U11") (pin "B12") (pinfunction "PS_MIO48_501_B12") (pintype "passive"))
    )
    (net (code "181") (name "unconnected-(U11-PS_MIO49_501-PadD13)") (class "Default")
      (node (ref "U11") (pin "D13") (pinfunction "PS_MIO49_501_D13") (pintype "passive"))
    )
    (net (code "182") (name "unconnected-(U11-PS_MIO52_501-PadA12)") (class "Default")
      (node (ref "U11") (pin "A12") (pinfunction "PS_MIO52_501_A12") (pintype "passive"))
    )
    (net (code "183") (name "unconnected-(U11-PS_MIO53_501-PadC13)") (class "Default")
      (node (ref "U11") (pin "C13") (pinfunction "PS_MIO53_501_C13") (pintype "passive"))
    )
    (net (code "184") (name "unconnected-(U11-PS_POR_B_500-PadC9)") (class "Default")
      (node (ref "U11") (pin "C9") (pinfunction "PS_POR_B_500_C9") (pintype "passive"))
    )
    (net (code "185") (name "unconnected-(U11-PS_SRST_B_501-PadB11)") (class "Default")
      (node (ref "U11") (pin "B11") (pinfunction "PS_SRST_B_501_B11") (pintype "passive"))
    )
    (net (code "186") (name "unconnected-(U11-RSVDGND-PadE8)") (class "Default")
      (node (ref "U11") (pin "E8") (pinfunction "RSVDGND_E8") (pintype "passive"))
    )
    (net (code "187") (name "unconnected-(U11-RSVDVCC1-PadG4)") (class "Default")
      (node (ref "U11") (pin "G4") (pinfunction "RSVDVCC1_G4") (pintype "passive"))
    )
    (net (code "188") (name "unconnected-(U11-RSVDVCC2-PadJ4)") (class "Default")
      (node (ref "U11") (pin "J4") (pinfunction "RSVDVCC2_J4") (pintype "passive"))
    )
    (net (code "189") (name "unconnected-(U11-RSVDVCC3-PadH4)") (class "Default")
      (node (ref "U11") (pin "H4") (pinfunction "RSVDVCC3_H4") (pintype "passive"))
    )
    (net (code "190") (name "unconnected-(U11-TCK_0-PadG9)") (class "Default")
      (node (ref "U11") (pin "G9") (pinfunction "TCK_0_G9") (pintype "passive"))
    )
    (net (code "191") (name "unconnected-(U11-TDI_0-PadL7)") (class "Default")
      (node (ref "U11") (pin "L7") (pinfunction "TDI_0_L7") (pintype "passive"))
    )
    (net (code "192") (name "unconnected-(U11-TDO_0-PadL8)") (class "Default")
      (node (ref "U11") (pin "L8") (pinfunction "TDO_0_L8") (pintype "passive"))
    )
    (net (code "193") (name "unconnected-(U11-TMS_0-PadL9)") (class "Default")
      (node (ref "U11") (pin "L9") (pinfunction "TMS_0_L9") (pintype "passive"))
    )
    (net (code "194") (name "unconnected-(U11-VCCADC_0-PadF7)") (class "Default")
      (node (ref "U11") (pin "F7") (pinfunction "VCCADC_0_F7") (pintype "passive"))
    )
    (net (code "195") (name "unconnected-(U11-VCCAUX_1-PadH9)") (class "Default")
      (node (ref "U11") (pin "H9") (pinfunction "VCCAUX_1_H9") (pintype "passive"))
    )
    (net (code "196") (name "unconnected-(U11-VCCAUX_2-PadJ8)") (class "Default")
      (node (ref "U11") (pin "J8") (pinfunction "VCCAUX_2_J8") (pintype "passive"))
    )
    (net (code "197") (name "unconnected-(U11-VCCAUX_3-PadK9)") (class "Default")
      (node (ref "U11") (pin "K9") (pinfunction "VCCAUX_3_K9") (pintype "passive"))
    )
    (net (code "198") (name "unconnected-(U11-VCCBATT_0-PadE6)") (class "Default")
      (node (ref "U11") (pin "E6") (pinfunction "VCCBATT_0_E6") (pintype "passive"))
    )
    (net (code "199") (name "unconnected-(U11-VCCINT_1-PadE10)") (class "Default")
      (node (ref "U11") (pin "E10") (pinfunction "VCCINT_1_E10") (pintype "passive"))
    )
    (net (code "200") (name "unconnected-(U11-VCCINT_2-PadF9)") (class "Default")
      (node (ref "U11") (pin "F9") (pinfunction "VCCINT_2_F9") (pintype "passive"))
    )
    (net (code "201") (name "unconnected-(U11-VCCINT_3-PadG10)") (class "Default")
      (node (ref "U11") (pin "G10") (pinfunction "VCCINT_3_G10") (pintype "passive"))
    )
    (net (code "202") (name "unconnected-(U11-VCCINT_4-PadJ10)") (class "Default")
      (node (ref "U11") (pin "J10") (pinfunction "VCCINT_4_J10") (pintype "passive"))
    )
    (net (code "203") (name "unconnected-(U11-VCCINT_5-PadL10)") (class "Default")
      (node (ref "U11") (pin "L10") (pinfunction "VCCINT_5_L10") (pintype "passive"))
    )
    (net (code "204") (name "unconnected-(U11-VCCO_0-PadK8)") (class "Default")
      (node (ref "U11") (pin "K8") (pinfunction "VCCO_0_K8") (pintype "passive"))
    )
    (net (code "205") (name "unconnected-(U11-VCCO_34_1-PadJ12)") (class "Default")
      (node (ref "U11") (pin "J12") (pinfunction "VCCO_34_1_J12") (pintype "passive"))
    )
    (net (code "206") (name "unconnected-(U11-VCCO_34_2-PadM13)") (class "Default")
      (node (ref "U11") (pin "M13") (pinfunction "VCCO_34_2_M13") (pintype "passive"))
    )
    (net (code "207") (name "unconnected-(U11-VCCO_34_3-PadN10)") (class "Default")
      (node (ref "U11") (pin "N10") (pinfunction "VCCO_34_3_N10") (pintype "passive"))
    )
    (net (code "208") (name "unconnected-(U11-VCCO_34_4-PadP7)") (class "Default")
      (node (ref "U11") (pin "P7") (pinfunction "VCCO_34_4_P7") (pintype "passive"))
    )
    (net (code "209") (name "unconnected-(U11-VCCO_34_5-PadR14)") (class "Default")
      (node (ref "U11") (pin "R14") (pinfunction "VCCO_34_5_R14") (pintype "passive"))
    )
    (net (code "210") (name "unconnected-(U11-VCCO_35_1-PadF11)") (class "Default")
      (node (ref "U11") (pin "F11") (pinfunction "VCCO_35_1_F11") (pintype "passive"))
    )
    (net (code "211") (name "unconnected-(U11-VCCO_35_2-PadH15)") (class "Default")
      (node (ref "U11") (pin "H15") (pinfunction "VCCO_35_2_H15") (pintype "passive"))
    )
    (net (code "212") (name "unconnected-(U11-VCCO_DDR_502_1-PadB3)") (class "Default")
      (node (ref "U11") (pin "B3") (pinfunction "VCCO_DDR_502_1_B3") (pintype "passive"))
    )
    (net (code "213") (name "unconnected-(U11-VCCO_DDR_502_2-PadE4)") (class "Default")
      (node (ref "U11") (pin "E4") (pinfunction "VCCO_DDR_502_2_E4") (pintype "passive"))
    )
    (net (code "214") (name "unconnected-(U11-VCCO_DDR_502_3-PadF1)") (class "Default")
      (node (ref "U11") (pin "F1") (pinfunction "VCCO_DDR_502_3_F1") (pintype "passive"))
    )
    (net (code "215") (name "unconnected-(U11-VCCO_DDR_502_4-PadJ2)") (class "Default")
      (node (ref "U11") (pin "J2") (pinfunction "VCCO_DDR_502_4_J2") (pintype "passive"))
    )
    (net (code "216") (name "unconnected-(U11-VCCO_DDR_502_5-PadM3)") (class "Default")
      (node (ref "U11") (pin "M3") (pinfunction "VCCO_DDR_502_5_M3") (pintype "passive"))
    )
    (net (code "217") (name "unconnected-(U11-VCCO_DDR_502_6-PadR4)") (class "Default")
      (node (ref "U11") (pin "R4") (pinfunction "VCCO_DDR_502_6_R4") (pintype "passive"))
    )
    (net (code "218") (name "unconnected-(U11-VCCO_MIO0_500_1-PadA6)") (class "Default")
      (node (ref "U11") (pin "A6") (pinfunction "VCCO_MIO0_500_1_A6") (pintype "passive"))
    )
    (net (code "219") (name "unconnected-(U11-VCCO_MIO0_500_2-PadD7)") (class "Default")
      (node (ref "U11") (pin "D7") (pinfunction "VCCO_MIO0_500_2_D7") (pintype "passive"))
    )
    (net (code "220") (name "unconnected-(U11-VCCO_MIO1_501_1-PadB13)") (class "Default")
      (node (ref "U11") (pin "B13") (pinfunction "VCCO_MIO1_501_1_B13") (pintype "passive"))
    )
    (net (code "221") (name "unconnected-(U11-VCCO_MIO1_501_2-PadC10)") (class "Default")
      (node (ref "U11") (pin "C10") (pinfunction "VCCO_MIO1_501_2_C10") (pintype "passive"))
    )
    (net (code "222") (name "unconnected-(U11-VCCO_MIO1_501_3-PadE14)") (class "Default")
      (node (ref "U11") (pin "E14") (pinfunction "VCCO_MIO1_501_3_E14") (pintype "passive"))
    )
    (net (code "223") (name "unconnected-(U11-VCCPAUX_1-PadJ6)") (class "Default")
      (node (ref "U11") (pin "J6") (pinfunction "VCCPAUX_1_J6") (pintype "passive"))
    )
    (net (code "224") (name "unconnected-(U11-VCCPAUX_2-PadL6)") (class "Default")
      (node (ref "U11") (pin "L6") (pinfunction "VCCPAUX_2_L6") (pintype "passive"))
    )
    (net (code "225") (name "unconnected-(U11-VCCPINT_1-PadG6)") (class "Default")
      (node (ref "U11") (pin "G6") (pinfunction "VCCPINT_1_G6") (pintype "passive"))
    )
    (net (code "226") (name "unconnected-(U11-VCCPINT_2-PadH5)") (class "Default")
      (node (ref "U11") (pin "H5") (pinfunction "VCCPINT_2_H5") (pintype "passive"))
    )
    (net (code "227") (name "unconnected-(U11-VCCPINT_3-PadK5)") (class "Default")
      (node (ref "U11") (pin "K5") (pinfunction "VCCPINT_3_K5") (pintype "passive"))
    )
    (net (code "228") (name "unconnected-(U11-VCCPLL-PadF5)") (class "Default")
      (node (ref "U11") (pin "F5") (pinfunction "VCCPLL_F5") (pintype "passive"))
    )
    (net (code "229") (name "unconnected-(U11-VN_0-PadH8)") (class "Default")
      (node (ref "U11") (pin "H8") (pinfunction "VN_0_H8") (pintype "passive"))
    )
    (net (code "230") (name "unconnected-(U11-VP_0-PadG7)") (class "Default")
      (node (ref "U11") (pin "G7") (pinfunction "VP_0_G7") (pintype "passive"))
    )
    (net (code "231") (name "unconnected-(U11-VREFN_0-PadG8)") (class "Default")
      (node (ref "U11") (pin "G8") (pinfunction "VREFN_0_G8") (pintype "passive"))
    )
    (net (code "232") (name "unconnected-(U11-VREFP_0-PadH7)") (class "Default")
      (node (ref "U11") (pin "H7") (pinfunction "VREFP_0_H7") (pintype "passive"))
    )
  )
)
